# Adafruit_Bluefruit_LE_nRF8001_v2.net
KiCad netlist of a schematic drawn in EAGLE
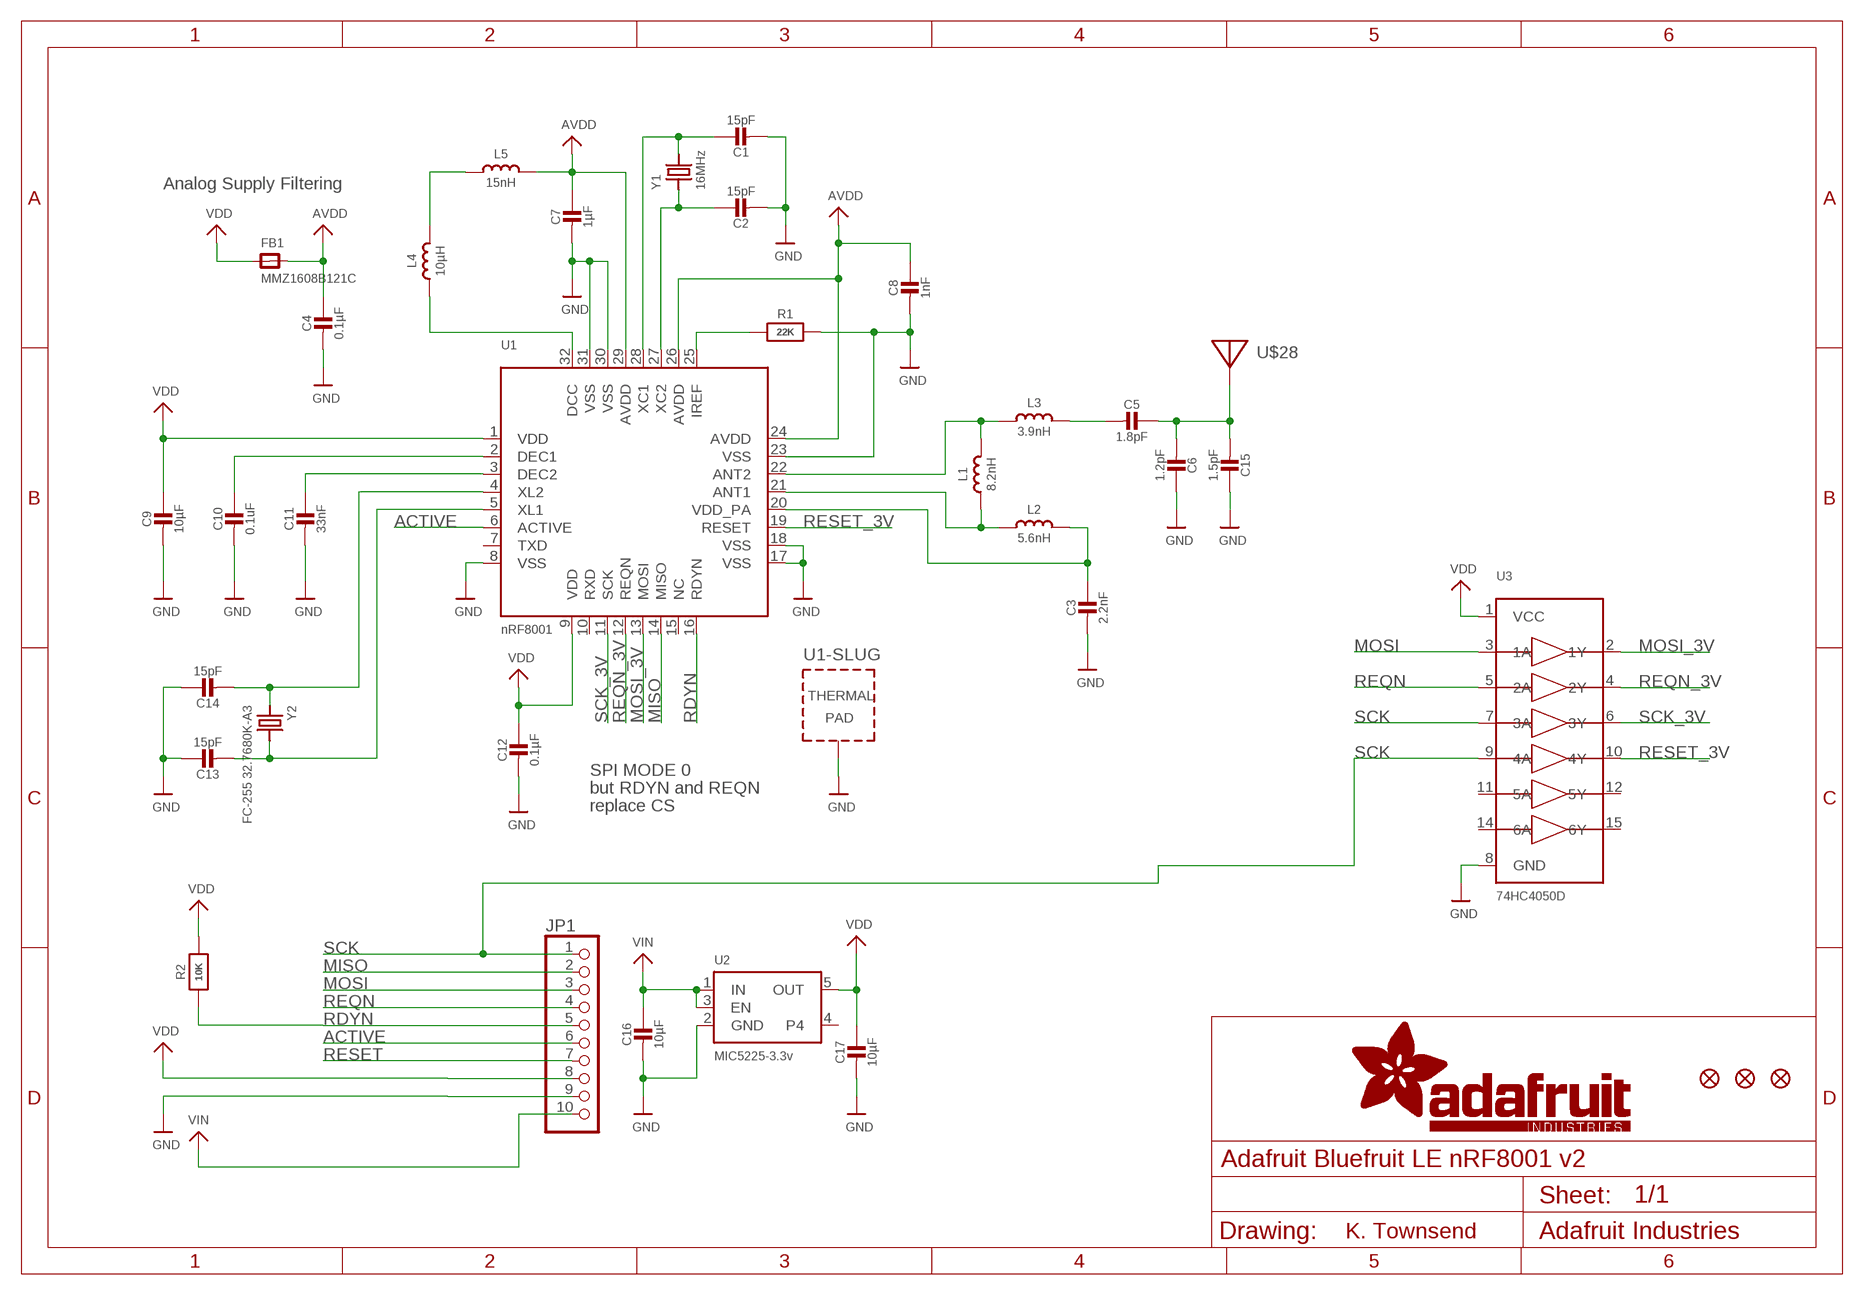
[diagram p0: schematic, sheet 1]

(export (version "E")
  (design (tool "Eeschema 10.0.6"))
  (components
    (comp (ref "C1")
      (value "15pF")
      (footprint "eagle-import:0805-NO")
      (libsource (lib "eagle-import") (part "CAP_CERAMIC0805-NOOUTLINE"))
    )
    (comp (ref "C2")
      (value "15pF")
      (footprint "eagle-import:0805-NO")
      (libsource (lib "eagle-import") (part "CAP_CERAMIC0805-NOOUTLINE"))
    )
    (comp (ref "C3")
      (value "2.2nF")
      (footprint "eagle-import:_0402")
      (libsource (lib "eagle-import") (part "CAP_CERAMIC_0402"))
    )
    (comp (ref "C4")
      (value "0.1µF")
      (footprint "eagle-import:0805-NO")
      (libsource (lib "eagle-import") (part "CAP_CERAMIC0805-NOOUTLINE"))
    )
    (comp (ref "C5")
      (value "1.8pF")
      (footprint "eagle-import:_0402MP")
      (libsource (lib "eagle-import") (part "CAP_CERAMIC_0402MP"))
    )
    (comp (ref "C6")
      (value "1.2pF")
      (footprint "eagle-import:_0402MP")
      (libsource (lib "eagle-import") (part "CAP_CERAMIC_0402MP"))
    )
    (comp (ref "C7")
      (value "1µF")
      (footprint "eagle-import:0805-NO")
      (libsource (lib "eagle-import") (part "CAP_CERAMIC0805-NOOUTLINE"))
    )
    (comp (ref "C8")
      (value "1nF")
      (footprint "eagle-import:_0603")
      (libsource (lib "eagle-import") (part "CAP_CERAMIC_0603"))
    )
    (comp (ref "C9")
      (value "10µF")
      (footprint "eagle-import:0805-NO")
      (libsource (lib "eagle-import") (part "CAP_CERAMIC0805-NOOUTLINE"))
    )
    (comp (ref "C10")
      (value "0.1uF")
      (footprint "eagle-import:0805-NO")
      (libsource (lib "eagle-import") (part "CAP_CERAMIC0805-NOOUTLINE"))
    )
    (comp (ref "C11")
      (value "33nF")
      (footprint "eagle-import:0805-NO")
      (libsource (lib "eagle-import") (part "CAP_CERAMIC0805-NOOUTLINE"))
    )
    (comp (ref "C12")
      (value "0.1µF")
      (footprint "eagle-import:0805-NO")
      (libsource (lib "eagle-import") (part "CAP_CERAMIC0805-NOOUTLINE"))
    )
    (comp (ref "C13")
      (value "15pF")
      (footprint "eagle-import:0805-NO")
      (libsource (lib "eagle-import") (part "CAP_CERAMIC0805-NOOUTLINE"))
    )
    (comp (ref "C14")
      (value "15pF")
      (footprint "eagle-import:0805-NO")
      (libsource (lib "eagle-import") (part "CAP_CERAMIC0805-NOOUTLINE"))
    )
    (comp (ref "C15")
      (value "1.5pF")
      (footprint "eagle-import:_0402MP")
      (libsource (lib "eagle-import") (part "CAP_CERAMIC_0402MP"))
    )
    (comp (ref "C16")
      (value "10µF")
      (footprint "eagle-import:0805-NO")
      (libsource (lib "eagle-import") (part "CAP_CERAMIC0805-NOOUTLINE"))
    )
    (comp (ref "C17")
      (value "10µF")
      (footprint "eagle-import:0805-NO")
      (libsource (lib "eagle-import") (part "CAP_CERAMIC0805-NOOUTLINE"))
    )
    (comp (ref "FB1")
      (value "MMZ1608B121C")
      (footprint "eagle-import:0805")
      (libsource (lib "eagle-import") (part "FERRITE0805"))
    )
    (comp (ref "FID1")
      (value "FIDUCIAL\"\"")
      (footprint "eagle-import:FIDUCIAL_1MM")
      (libsource (lib "eagle-import") (part "FIDUCIAL{dblquote}{dblquote}"))
    )
    (comp (ref "FID2")
      (value "FIDUCIAL\"\"")
      (footprint "eagle-import:FIDUCIAL_1MM")
      (libsource (lib "eagle-import") (part "FIDUCIAL{dblquote}{dblquote}"))
    )
    (comp (ref "FID3")
      (value "FIDUCIAL\"\"")
      (footprint "eagle-import:FIDUCIAL_1MM")
      (fields (field (name "BOM") "EXCLUDE"))
      (libsource (lib "eagle-import") (part "FIDUCIAL{dblquote}{dblquote}"))
    )
    (comp (ref "JP1")
      (value "HEADER-1X1070MIL")
      (footprint "eagle-import:1X10_ROUND70")
      (libsource (lib "eagle-import") (part "HEADER-1X1070MIL"))
    )
    (comp (ref "L1")
      (value "8.2nH")
      (footprint "eagle-import:_0402")
      (libsource (lib "eagle-import") (part "INDUCTOR_0402"))
    )
    (comp (ref "L2")
      (value "5.6nH")
      (footprint "eagle-import:_0402")
      (libsource (lib "eagle-import") (part "INDUCTOR_0402"))
    )
    (comp (ref "L3")
      (value "3.9nH")
      (footprint "eagle-import:_0402")
      (libsource (lib "eagle-import") (part "INDUCTOR_0402"))
    )
    (comp (ref "L4")
      (value "10µH")
      (footprint "eagle-import:_0603")
      (libsource (lib "eagle-import") (part "INDUCTOR_0603"))
    )
    (comp (ref "L5")
      (value "15nH")
      (footprint "eagle-import:_0603")
      (libsource (lib "eagle-import") (part "INDUCTOR_0603"))
    )
    (comp (ref "R1")
      (value "22K")
      (footprint "eagle-import:_0805MP")
      (libsource (lib "eagle-import") (part "RESISTOR_0805MP"))
    )
    (comp (ref "R2")
      (value "10K")
      (footprint "eagle-import:0805-NO")
      (libsource (lib "eagle-import") (part "RESISTOR0805_NOOUTLINE"))
    )
    (comp (ref "U$28")
      (value "ANTENNA_PCBNRF8001_1.6MM")
      (footprint "eagle-import:ANT_PCB_2.4GHZ_NRF8001_1.6MM_1OZ")
      (libsource (lib "eagle-import") (part "ANTENNA_PCBNRF8001_1.6MM"))
    )
    (comp (ref "U1")
      (value "nRF8001")
      (footprint "eagle-import:QFN32_5MM")
      (libsource (lib "eagle-import") (part "NRF8001"))
    )
    (comp (ref "U2")
      (value "MIC5225-3.3v")
      (footprint "eagle-import:SOT23-5")
      (libsource (lib "eagle-import") (part "VREG_SOT23-5"))
    )
    (comp (ref "U3")
      (value "74HC4050D")
      (footprint "eagle-import:TSSOP16")
      (libsource (lib "eagle-import") (part "74HC4050DTSSOP"))
    )
    (comp (ref "Y1")
      (value "16MHz")
      (footprint "eagle-import:CRYSTAL_3.2X2.5")
      (libsource (lib "eagle-import") (part "CRYSTAL3.2X2.5"))
    )
    (comp (ref "Y2")
      (value "FC-255 32.7680K-A3")
      (footprint "eagle-import:CRYSTAL_8X3.8")
      (libsource (lib "eagle-import") (part "CRYSTAL8.0X3.8"))
    )
  )
  (nets
    (net (code "1") (name "/ACTIVE") (class "Default")
      (node (ref "JP1") (pin "6") (pinfunction "6_6") (pintype "passive"))
      (node (ref "U1") (pin "6") (pinfunction "ACTIVE_6") (pintype "output"))
    )
    (net (code "2") (name "/MISO") (class "Default")
      (node (ref "JP1") (pin "2") (pinfunction "2_2") (pintype "passive"))
      (node (ref "U1") (pin "14") (pinfunction "MISO_14") (pintype "output"))
    )
    (net (code "3") (name "/MOSI") (class "Default")
      (node (ref "JP1") (pin "3") (pinfunction "3_3") (pintype "passive"))
      (node (ref "U3") (pin "3") (pinfunction "1A_3") (pintype "bidirectional"))
    )
    (net (code "4") (name "/MOSI_3V") (class "Default")
      (node (ref "U1") (pin "13") (pinfunction "MOSI_13") (pintype "input"))
      (node (ref "U3") (pin "2") (pinfunction "1Y_2") (pintype "bidirectional"))
    )
    (net (code "5") (name "/RDYN") (class "Default")
      (node (ref "JP1") (pin "5") (pinfunction "5_5") (pintype "passive"))
      (node (ref "R2") (pin "1") (pinfunction "1_1") (pintype "passive"))
      (node (ref "U1") (pin "16") (pinfunction "RDYN_16") (pintype "output"))
    )
    (net (code "6") (name "/REQN") (class "Default")
      (node (ref "JP1") (pin "4") (pinfunction "4_4") (pintype "passive"))
      (node (ref "U3") (pin "5") (pinfunction "2A_5") (pintype "bidirectional"))
    )
    (net (code "7") (name "/REQN_3V") (class "Default")
      (node (ref "U1") (pin "12") (pinfunction "REQN_12") (pintype "input"))
      (node (ref "U3") (pin "4") (pinfunction "2Y_4") (pintype "bidirectional"))
    )
    (net (code "8") (name "/RESET") (class "Default")
      (node (ref "JP1") (pin "7") (pinfunction "7_7") (pintype "passive"))
    )
    (net (code "9") (name "/RESET_3V") (class "Default")
      (node (ref "U1") (pin "19") (pinfunction "RESET_19") (pintype "input"))
      (node (ref "U3") (pin "10") (pinfunction "4Y_10") (pintype "bidirectional"))
    )
    (net (code "10") (name "/SCK") (class "Default")
      (node (ref "JP1") (pin "1") (pinfunction "1_1") (pintype "passive"))
      (node (ref "U3") (pin "7") (pinfunction "3A_7") (pintype "bidirectional"))
      (node (ref "U3") (pin "9") (pinfunction "4A_9") (pintype "bidirectional"))
    )
    (net (code "11") (name "/SCK_3V") (class "Default")
      (node (ref "U1") (pin "11") (pinfunction "SCK_11") (pintype "input"))
      (node (ref "U3") (pin "6") (pinfunction "3Y_6") (pintype "bidirectional"))
    )
    (net (code "12") (name "AVDD") (class "Default")
      (node (ref "C4") (pin "1") (pinfunction "1_1") (pintype "passive"))
      (node (ref "C7") (pin "1") (pinfunction "1_1") (pintype "passive"))
      (node (ref "C8") (pin "1") (pinfunction "1_1") (pintype "passive"))
      (node (ref "FB1") (pin "2") (pinfunction "P$2_2") (pintype "passive"))
      (node (ref "L5") (pin "2") (pinfunction "2_2") (pintype "passive"))
      (node (ref "U1") (pin "24") (pinfunction "AVDD_24") (pintype "power_in"))
      (node (ref "U1") (pin "26") (pinfunction "AVDD_26") (pintype "power_in"))
      (node (ref "U1") (pin "29") (pinfunction "AVDD_29") (pintype "power_in"))
    )
    (net (code "13") (name "GND") (class "Default")
      (node (ref "C1") (pin "2") (pinfunction "2_2") (pintype "passive"))
      (node (ref "C10") (pin "2") (pinfunction "2_2") (pintype "passive"))
      (node (ref "C11") (pin "2") (pinfunction "2_2") (pintype "passive"))
      (node (ref "C12") (pin "2") (pinfunction "2_2") (pintype "passive"))
      (node (ref "C13") (pin "1") (pinfunction "1_1") (pintype "passive"))
      (node (ref "C14") (pin "1") (pinfunction "1_1") (pintype "passive"))
      (node (ref "C15") (pin "1") (pinfunction "1_1") (pintype "passive"))
      (node (ref "C16") (pin "2") (pinfunction "2_2") (pintype "passive"))
      (node (ref "C17") (pin "2") (pinfunction "2_2") (pintype "passive"))
      (node (ref "C2") (pin "2") (pinfunction "2_2") (pintype "passive"))
      (node (ref "C3") (pin "2") (pinfunction "2_2") (pintype "passive"))
      (node (ref "C4") (pin "2") (pinfunction "2_2") (pintype "passive"))
      (node (ref "C6") (pin "1") (pinfunction "1_1") (pintype "passive"))
      (node (ref "C7") (pin "2") (pinfunction "2_2") (pintype "passive"))
      (node (ref "C8") (pin "2") (pinfunction "2_2") (pintype "passive"))
      (node (ref "C9") (pin "2") (pinfunction "2_2") (pintype "passive"))
      (node (ref "JP1") (pin "9") (pinfunction "9_9") (pintype "passive"))
      (node (ref "R1") (pin "2") (pinfunction "2_2") (pintype "passive"))
      (node (ref "U1") (pin "17") (pinfunction "VSS_17") (pintype "power_in"))
      (node (ref "U1") (pin "18") (pinfunction "VSS_18") (pintype "power_in"))
      (node (ref "U1") (pin "23") (pinfunction "VSS_23") (pintype "power_in"))
      (node (ref "U1") (pin "30") (pinfunction "VSS_30") (pintype "power_in"))
      (node (ref "U1") (pin "31") (pinfunction "VSS_31") (pintype "power_in"))
      (node (ref "U1") (pin "33") (pinfunction "TP_33") (pintype "power_in"))
      (node (ref "U1") (pin "8") (pinfunction "VSS_8") (pintype "power_in"))
      (node (ref "U2") (pin "2") (pinfunction "GND_2") (pintype "power_in"))
      (node (ref "U3") (pin "8") (pinfunction "GND_8") (pintype "bidirectional"))
    )
    (net (code "14") (name "Net-(C5-Pad2)") (class "Default")
      (node (ref "C5") (pin "2") (pinfunction "2_2") (pintype "passive"))
      (node (ref "L3") (pin "2") (pinfunction "2_2") (pintype "passive"))
    )
    (net (code "15") (name "Net-(L4-Pad2)") (class "Default")
      (node (ref "L4") (pin "2") (pinfunction "2_2") (pintype "passive"))
      (node (ref "L5") (pin "1") (pinfunction "1_1") (pintype "passive"))
    )
    (net (code "16") (name "Net-(U$28-P$1)") (class "Default")
      (node (ref "C15") (pin "2") (pinfunction "2_2") (pintype "passive"))
      (node (ref "C5") (pin "1") (pinfunction "1_1") (pintype "passive"))
      (node (ref "C6") (pin "2") (pinfunction "2_2") (pintype "passive"))
      (node (ref "U$28") (pin "FEED") (pinfunction "P$1_FEED") (pintype "passive"))
    )
    (net (code "17") (name "Net-(U1B-ANT1)") (class "Default")
      (node (ref "L1") (pin "1") (pinfunction "1_1") (pintype "passive"))
      (node (ref "L2") (pin "1") (pinfunction "1_1") (pintype "passive"))
      (node (ref "U1") (pin "21") (pinfunction "ANT1_21") (pintype "bidirectional"))
    )
    (net (code "18") (name "Net-(U1B-ANT2)") (class "Default")
      (node (ref "L1") (pin "2") (pinfunction "2_2") (pintype "passive"))
      (node (ref "L3") (pin "1") (pinfunction "1_1") (pintype "passive"))
      (node (ref "U1") (pin "22") (pinfunction "ANT2_22") (pintype "bidirectional"))
    )
    (net (code "19") (name "Net-(U1B-DCC)") (class "Default")
      (node (ref "L4") (pin "1") (pinfunction "1_1") (pintype "passive"))
      (node (ref "U1") (pin "32") (pinfunction "DCC_32") (pintype "bidirectional"))
    )
    (net (code "20") (name "Net-(U1B-DEC1)") (class "Default")
      (node (ref "C10") (pin "1") (pinfunction "1_1") (pintype "passive"))
      (node (ref "U1") (pin "2") (pinfunction "DEC1_2") (pintype "bidirectional"))
    )
    (net (code "21") (name "Net-(U1B-DEC2)") (class "Default")
      (node (ref "C11") (pin "1") (pinfunction "1_1") (pintype "passive"))
      (node (ref "U1") (pin "3") (pinfunction "DEC2_3") (pintype "bidirectional"))
    )
    (net (code "22") (name "Net-(U1B-IREF)") (class "Default")
      (node (ref "R1") (pin "1") (pinfunction "1_1") (pintype "passive"))
      (node (ref "U1") (pin "25") (pinfunction "IREF_25") (pintype "output"))
    )
    (net (code "23") (name "Net-(U1B-VDD_PA)") (class "Default")
      (node (ref "C3") (pin "1") (pinfunction "1_1") (pintype "passive"))
      (node (ref "L2") (pin "2") (pinfunction "2_2") (pintype "passive"))
      (node (ref "U1") (pin "20") (pinfunction "VDD_PA_20") (pintype "bidirectional"))
    )
    (net (code "24") (name "Net-(U1B-XC1)") (class "Default")
      (node (ref "C1") (pin "1") (pinfunction "1_1") (pintype "passive"))
      (node (ref "U1") (pin "28") (pinfunction "XC1_28") (pintype "input"))
      (node (ref "Y1") (pin "2") (pinfunction "2_2") (pintype "passive"))
    )
    (net (code "25") (name "Net-(U1B-XC2)") (class "Default")
      (node (ref "C2") (pin "1") (pinfunction "1_1") (pintype "passive"))
      (node (ref "U1") (pin "27") (pinfunction "XC2_27") (pintype "output"))
      (node (ref "Y1") (pin "1") (pinfunction "1_1") (pintype "passive"))
    )
    (net (code "26") (name "Net-(U1B-XL1)") (class "Default")
      (node (ref "C13") (pin "2") (pinfunction "2_2") (pintype "passive"))
      (node (ref "U1") (pin "5") (pinfunction "XL1_5") (pintype "input"))
      (node (ref "Y2") (pin "P$4") (pinfunction "2_P$4") (pintype "passive"))
    )
    (net (code "27") (name "Net-(U1B-XL2)") (class "Default")
      (node (ref "C14") (pin "2") (pinfunction "2_2") (pintype "passive"))
      (node (ref "U1") (pin "4") (pinfunction "XL2_4") (pintype "output"))
      (node (ref "Y2") (pin "P$1") (pinfunction "1_P$1") (pintype "passive"))
    )
    (net (code "28") (name "VDD") (class "Default")
      (node (ref "C12") (pin "1") (pinfunction "1_1") (pintype "passive"))
      (node (ref "C17") (pin "1") (pinfunction "1_1") (pintype "passive"))
      (node (ref "C9") (pin "1") (pinfunction "1_1") (pintype "passive"))
      (node (ref "FB1") (pin "1") (pinfunction "P$1_1") (pintype "passive"))
      (node (ref "JP1") (pin "8") (pinfunction "8_8") (pintype "passive"))
      (node (ref "R2") (pin "2") (pinfunction "2_2") (pintype "passive"))
      (node (ref "U1") (pin "1") (pinfunction "VDD_1") (pintype "power_in"))
      (node (ref "U1") (pin "9") (pinfunction "VDD_9") (pintype "power_in"))
      (node (ref "U2") (pin "5") (pinfunction "OUT_5") (pintype "power_in"))
      (node (ref "U3") (pin "1") (pinfunction "VCC_1") (pintype "bidirectional"))
    )
    (net (code "29") (name "VIN") (class "Default")
      (node (ref "C16") (pin "1") (pinfunction "1_1") (pintype "passive"))
      (node (ref "JP1") (pin "10") (pinfunction "10_10") (pintype "passive"))
      (node (ref "U2") (pin "1") (pinfunction "IN_1") (pintype "power_in"))
      (node (ref "U2") (pin "3") (pinfunction "EN_3") (pintype "input"))
    )
    (net (code "30") (name "unconnected-(U1B-NC-Pad15)") (class "Default")
      (node (ref "U1") (pin "15") (pinfunction "NC_15") (pintype "no_connect"))
    )
    (net (code "31") (name "unconnected-(U1B-RXD-Pad10)") (class "Default")
      (node (ref "U1") (pin "10") (pinfunction "RXD_10") (pintype "input"))
    )
    (net (code "32") (name "unconnected-(U1B-TXD-Pad7)") (class "Default")
      (node (ref "U1") (pin "7") (pinfunction "TXD_7") (pintype "output"))
    )
    (net (code "33") (name "unconnected-(U2-P4-Pad4)") (class "Default")
      (node (ref "U2") (pin "4") (pinfunction "P4_4") (pintype "bidirectional"))
    )
    (net (code "34") (name "unconnected-(U3-5A-Pad11)") (class "Default")
      (node (ref "U3") (pin "11") (pinfunction "5A_11") (pintype "bidirectional"))
    )
    (net (code "35") (name "unconnected-(U3-5Y-Pad12)") (class "Default")
      (node (ref "U3") (pin "12") (pinfunction "5Y_12") (pintype "bidirectional"))
    )
    (net (code "36") (name "unconnected-(U3-6A-Pad14)") (class "Default")
      (node (ref "U3") (pin "14") (pinfunction "6A_14") (pintype "bidirectional"))
    )
    (net (code "37") (name "unconnected-(U3-6Y-Pad15)") (class "Default")
      (node (ref "U3") (pin "15") (pinfunction "6Y_15") (pintype "bidirectional"))
    )
  )
)
